# PCB-BI8-2x2.net
KiCad netlist of a schematic drawn in EAGLE
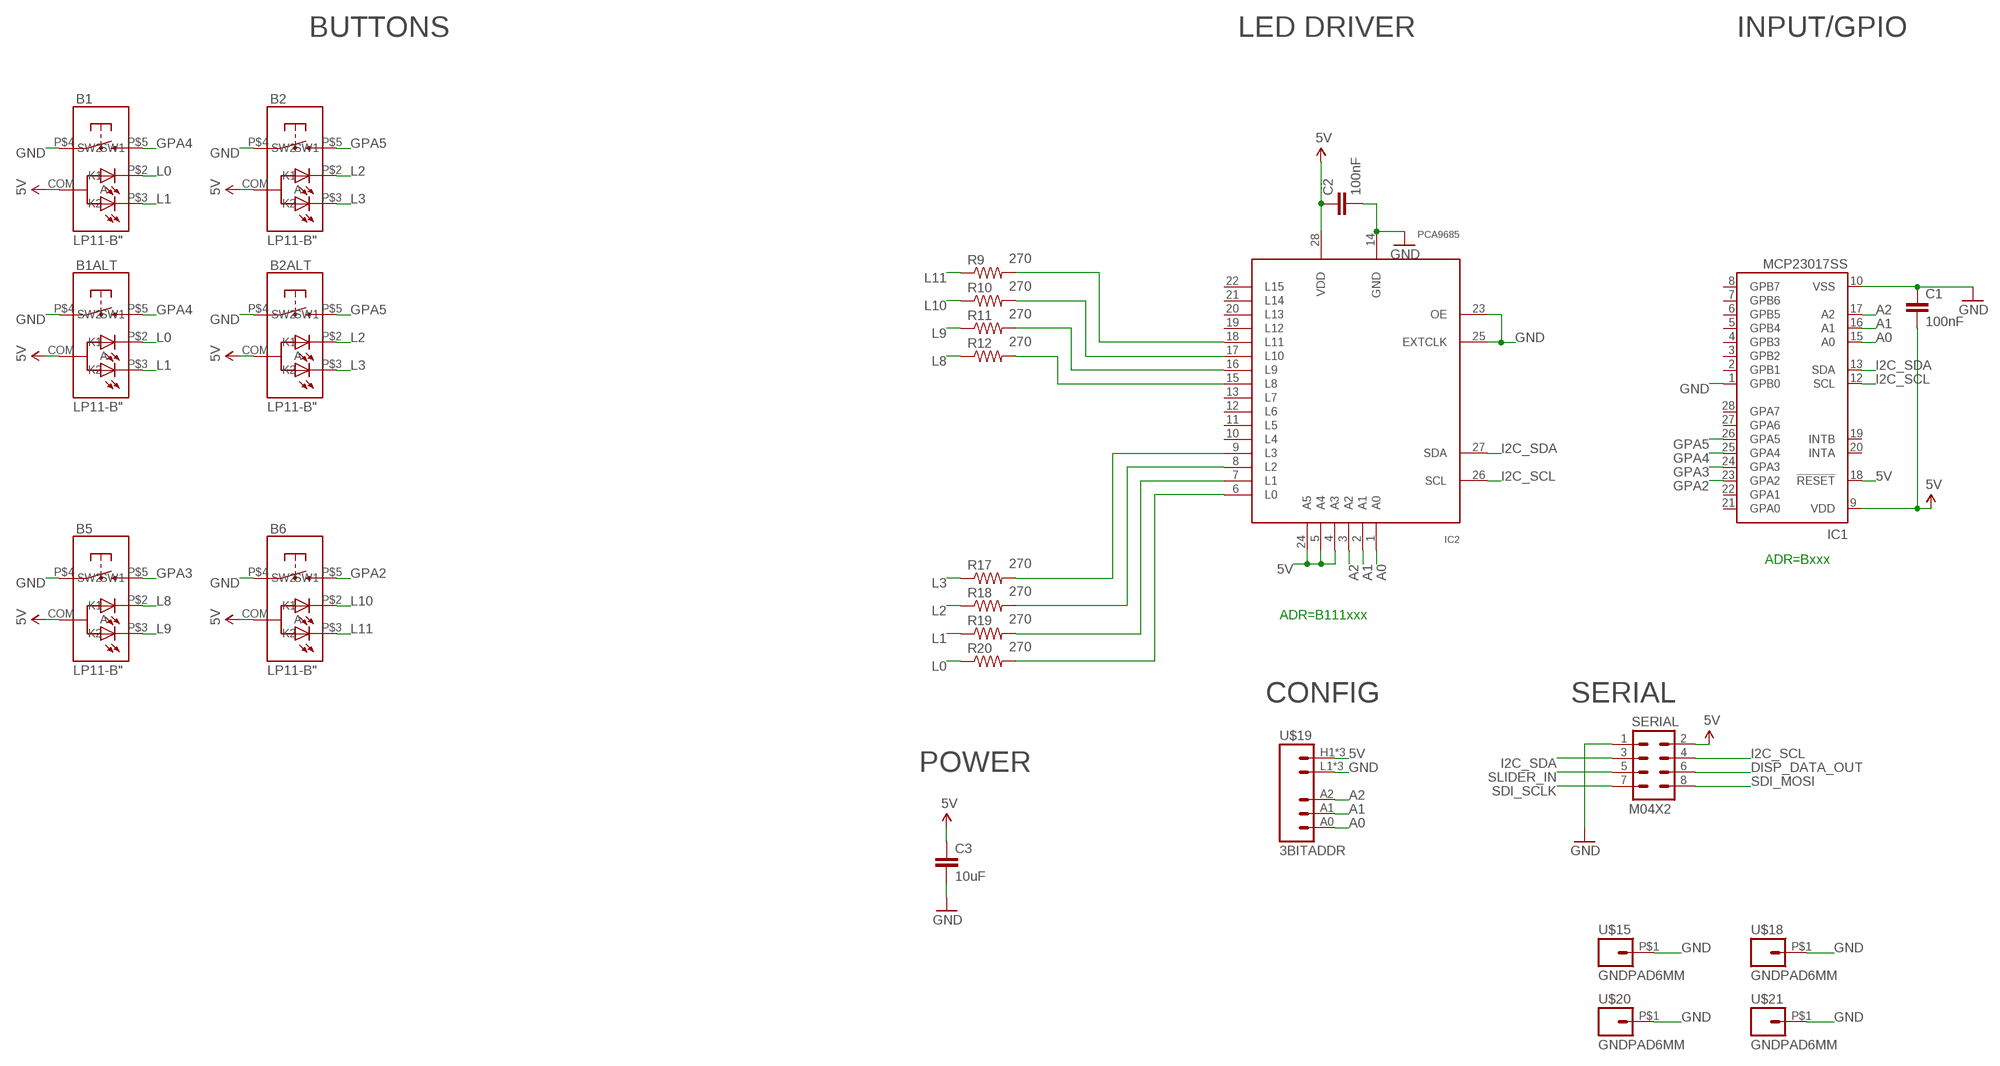
[diagram p0: schematic, sheet 1]

(export (version "E")
  (design (tool "Eeschema 10.0.6"))
  (components
    (comp (ref "B1")
      (value "LP11-B\"")
      (footprint "eagle-import:LP11")
      (libsource (lib "eagle-import") (part "LP11-B{dblquote}"))
    )
    (comp (ref "B1ALT")
      (value "LP11-B\"")
      (footprint "eagle-import:LP11")
      (libsource (lib "eagle-import") (part "LP11-B{dblquote}"))
    )
    (comp (ref "B2")
      (value "LP11-B\"")
      (footprint "eagle-import:LP11")
      (libsource (lib "eagle-import") (part "LP11-B{dblquote}"))
    )
    (comp (ref "B2ALT")
      (value "LP11-B\"")
      (footprint "eagle-import:LP11")
      (libsource (lib "eagle-import") (part "LP11-B{dblquote}"))
    )
    (comp (ref "B5")
      (value "LP11-B\"")
      (footprint "eagle-import:LP11")
      (libsource (lib "eagle-import") (part "LP11-B{dblquote}"))
    )
    (comp (ref "B6")
      (value "LP11-B\"")
      (footprint "eagle-import:LP11")
      (libsource (lib "eagle-import") (part "LP11-B{dblquote}"))
    )
    (comp (ref "C1")
      (value "100nF")
      (footprint "eagle-import:0603-CAP")
      (libsource (lib "eagle-import") (part "CAP0603-CAP"))
    )
    (comp (ref "C2")
      (value "100nF")
      (footprint "eagle-import:0603-CAP")
      (libsource (lib "eagle-import") (part "CAP0603-CAP"))
    )
    (comp (ref "C3")
      (value "10uF")
      (footprint "eagle-import:0805")
      (libsource (lib "eagle-import") (part "CAP0805"))
    )
    (comp (ref "IC1")
      (value "MCP23017SS")
      (footprint "eagle-import:SSOP28")
      (fields
        (field (name "MF") "MICROCHIP")
        (field (name "MPN") "MCP23017-E/SS")
        (field (name "MPN_1") "MCP23017-E/SS")
        (field (name "OC_FARNELL") "1467674")
        (field (name "OC_NEWARK") "31K2960")
      )
      (libsource (lib "eagle-import") (part "MCP23017SS"))
    )
    (comp (ref "IC2")
      (value "PCA9685")
      (footprint "eagle-import:TSSOP28")
      (libsource (lib "eagle-import") (part "PCA9685"))
    )
    (comp (ref "R9")
      (value "270")
      (footprint "eagle-import:0603-RES")
      (libsource (lib "eagle-import") (part "RESISTOR0603-RES"))
    )
    (comp (ref "R10")
      (value "270")
      (footprint "eagle-import:0603-RES")
      (libsource (lib "eagle-import") (part "RESISTOR0603-RES"))
    )
    (comp (ref "R11")
      (value "270")
      (footprint "eagle-import:0603-RES")
      (libsource (lib "eagle-import") (part "RESISTOR0603-RES"))
    )
    (comp (ref "R12")
      (value "270")
      (footprint "eagle-import:0603-RES")
      (libsource (lib "eagle-import") (part "RESISTOR0603-RES"))
    )
    (comp (ref "R17")
      (value "270")
      (footprint "eagle-import:0603-RES")
      (libsource (lib "eagle-import") (part "RESISTOR0603-RES"))
    )
    (comp (ref "R18")
      (value "270")
      (footprint "eagle-import:0603-RES")
      (libsource (lib "eagle-import") (part "RESISTOR0603-RES"))
    )
    (comp (ref "R19")
      (value "270")
      (footprint "eagle-import:0603-RES")
      (libsource (lib "eagle-import") (part "RESISTOR0603-RES"))
    )
    (comp (ref "R20")
      (value "270")
      (footprint "eagle-import:0603-RES")
      (libsource (lib "eagle-import") (part "RESISTOR0603-RES"))
    )
    (comp (ref "SERIAL")
      (value "M04X2")
      (footprint "eagle-import:2X4")
      (libsource (lib "eagle-import") (part "M04X2"))
    )
    (comp (ref "U$15")
      (value "GNDPAD6MM")
      (footprint "eagle-import:3.2MMPAD6MM")
      (libsource (lib "eagle-import") (part "GNDPAD6MM"))
    )
    (comp (ref "U$18")
      (value "GNDPAD6MM")
      (footprint "eagle-import:3.2MMPAD6MM")
      (libsource (lib "eagle-import") (part "GNDPAD6MM"))
    )
    (comp (ref "U$19")
      (value "3BITADDR")
      (footprint "eagle-import:3BITADDR")
      (libsource (lib "eagle-import") (part "3BITADDR"))
    )
    (comp (ref "U$20")
      (value "GNDPAD6MM")
      (footprint "eagle-import:3.2MMPAD6MM")
      (libsource (lib "eagle-import") (part "GNDPAD6MM"))
    )
    (comp (ref "U$21")
      (value "GNDPAD6MM")
      (footprint "eagle-import:3.2MMPAD6MM")
      (libsource (lib "eagle-import") (part "GNDPAD6MM"))
    )
  )
  (nets
    (net (code "1") (name "5V") (class "Default")
      (node (ref "B1") (pin "COM") (pinfunction "A_COM") (pintype "bidirectional"))
      (node (ref "B1ALT") (pin "COM") (pinfunction "A_COM") (pintype "bidirectional"))
      (node (ref "B2") (pin "COM") (pinfunction "A_COM") (pintype "bidirectional"))
      (node (ref "B2ALT") (pin "COM") (pinfunction "A_COM") (pintype "bidirectional"))
      (node (ref "B5") (pin "COM") (pinfunction "A_COM") (pintype "bidirectional"))
      (node (ref "B6") (pin "COM") (pinfunction "A_COM") (pintype "bidirectional"))
      (node (ref "C1") (pin "2") (pinfunction "2_2") (pintype "passive"))
      (node (ref "C2") (pin "1") (pinfunction "1_1") (pintype "passive"))
      (node (ref "C3") (pin "1") (pinfunction "1_1") (pintype "passive"))
      (node (ref "IC1") (pin "18") (pinfunction "~{RESET}_18") (pintype "input"))
      (node (ref "IC1") (pin "9") (pinfunction "VDD_9") (pintype "power_in"))
      (node (ref "IC2") (pin "24") (pinfunction "A5_24") (pintype "input"))
      (node (ref "IC2") (pin "28") (pinfunction "VDD_28") (pintype "power_in"))
      (node (ref "IC2") (pin "4") (pinfunction "A3_4") (pintype "input"))
      (node (ref "IC2") (pin "5") (pinfunction "A4_5") (pintype "input"))
      (node (ref "SERIAL") (pin "2") (pinfunction "2_2") (pintype "passive"))
      (node (ref "U$19") (pin "H1") (pinfunction "VCC_H1") (pintype "passive"))
      (node (ref "U$19") (pin "H2") (pinfunction "VCC_H2") (pintype "passive"))
      (node (ref "U$19") (pin "H3") (pinfunction "VCC_H3") (pintype "passive"))
    )
    (net (code "2") (name "A0") (class "Default")
      (node (ref "IC1") (pin "15") (pinfunction "A0_15") (pintype "input"))
      (node (ref "IC2") (pin "1") (pinfunction "A0_1") (pintype "input"))
      (node (ref "U$19") (pin "A0") (pinfunction "A0_A0") (pintype "passive"))
    )
    (net (code "3") (name "A1") (class "Default")
      (node (ref "IC1") (pin "16") (pinfunction "A1_16") (pintype "input"))
      (node (ref "IC2") (pin "2") (pinfunction "A1_2") (pintype "input"))
      (node (ref "U$19") (pin "A1") (pinfunction "A1_A1") (pintype "passive"))
    )
    (net (code "4") (name "A2") (class "Default")
      (node (ref "IC1") (pin "17") (pinfunction "A2_17") (pintype "input"))
      (node (ref "IC2") (pin "3") (pinfunction "A2_3") (pintype "input"))
      (node (ref "U$19") (pin "A2") (pinfunction "A2_A2") (pintype "passive"))
    )
    (net (code "5") (name "DISP_DATA_OUT") (class "Default")
      (node (ref "SERIAL") (pin "6") (pinfunction "6_6") (pintype "passive"))
    )
    (net (code "6") (name "GND") (class "Default")
      (node (ref "B1") (pin "P$4") (pinfunction "SW1_P$4") (pintype "bidirectional"))
      (node (ref "B1ALT") (pin "P$4") (pinfunction "SW1_P$4") (pintype "bidirectional"))
      (node (ref "B2") (pin "P$4") (pinfunction "SW1_P$4") (pintype "bidirectional"))
      (node (ref "B2ALT") (pin "P$4") (pinfunction "SW1_P$4") (pintype "bidirectional"))
      (node (ref "B5") (pin "P$4") (pinfunction "SW1_P$4") (pintype "bidirectional"))
      (node (ref "B6") (pin "P$4") (pinfunction "SW1_P$4") (pintype "bidirectional"))
      (node (ref "C1") (pin "1") (pinfunction "1_1") (pintype "passive"))
      (node (ref "C2") (pin "2") (pinfunction "2_2") (pintype "passive"))
      (node (ref "C3") (pin "2") (pinfunction "2_2") (pintype "passive"))
      (node (ref "IC1") (pin "1") (pinfunction "GPB0_1") (pintype "bidirectional"))
      (node (ref "IC1") (pin "10") (pinfunction "VSS_10") (pintype "power_in"))
      (node (ref "IC2") (pin "14") (pinfunction "GND_14") (pintype "power_in"))
      (node (ref "IC2") (pin "23") (pinfunction "OE_23") (pintype "input"))
      (node (ref "IC2") (pin "25") (pinfunction "EXTCLK_25") (pintype "input"))
      (node (ref "SERIAL") (pin "1") (pinfunction "1_1") (pintype "passive"))
      (node (ref "U$15") (pin "P$1") (pinfunction "1_P$1") (pintype "passive"))
      (node (ref "U$18") (pin "P$1") (pinfunction "1_P$1") (pintype "passive"))
      (node (ref "U$19") (pin "L1") (pinfunction "GND_L1") (pintype "passive"))
      (node (ref "U$19") (pin "L2") (pinfunction "GND_L2") (pintype "passive"))
      (node (ref "U$19") (pin "L3") (pinfunction "GND_L3") (pintype "passive"))
      (node (ref "U$20") (pin "P$1") (pinfunction "1_P$1") (pintype "passive"))
      (node (ref "U$21") (pin "P$1") (pinfunction "1_P$1") (pintype "passive"))
    )
    (net (code "7") (name "GPA2") (class "Default")
      (node (ref "B6") (pin "P$5") (pinfunction "SW2_P$5") (pintype "bidirectional"))
      (node (ref "IC1") (pin "23") (pinfunction "GPA2_23") (pintype "bidirectional"))
    )
    (net (code "8") (name "GPA3") (class "Default")
      (node (ref "B5") (pin "P$5") (pinfunction "SW2_P$5") (pintype "bidirectional"))
      (node (ref "IC1") (pin "24") (pinfunction "GPA3_24") (pintype "bidirectional"))
    )
    (net (code "9") (name "GPA4") (class "Default")
      (node (ref "B1") (pin "P$5") (pinfunction "SW2_P$5") (pintype "bidirectional"))
      (node (ref "B1ALT") (pin "P$5") (pinfunction "SW2_P$5") (pintype "bidirectional"))
      (node (ref "IC1") (pin "25") (pinfunction "GPA4_25") (pintype "bidirectional"))
    )
    (net (code "10") (name "GPA5") (class "Default")
      (node (ref "B2") (pin "P$5") (pinfunction "SW2_P$5") (pintype "bidirectional"))
      (node (ref "B2ALT") (pin "P$5") (pinfunction "SW2_P$5") (pintype "bidirectional"))
      (node (ref "IC1") (pin "26") (pinfunction "GPA5_26") (pintype "bidirectional"))
    )
    (net (code "11") (name "I2C_SCL") (class "Default")
      (node (ref "IC1") (pin "12") (pinfunction "SCL_12") (pintype "input"))
      (node (ref "IC2") (pin "26") (pinfunction "SCL_26") (pintype "input"))
      (node (ref "SERIAL") (pin "4") (pinfunction "4_4") (pintype "passive"))
    )
    (net (code "12") (name "I2C_SDA") (class "Default")
      (node (ref "IC1") (pin "13") (pinfunction "SDA_13") (pintype "bidirectional"))
      (node (ref "IC2") (pin "27") (pinfunction "SDA_27") (pintype "input"))
      (node (ref "SERIAL") (pin "3") (pinfunction "3_3") (pintype "passive"))
    )
    (net (code "13") (name "L0") (class "Default")
      (node (ref "B1") (pin "P$2") (pinfunction "K1_P$2") (pintype "bidirectional"))
      (node (ref "B1ALT") (pin "P$2") (pinfunction "K1_P$2") (pintype "bidirectional"))
      (node (ref "R20") (pin "1") (pinfunction "1_1") (pintype "passive"))
    )
    (net (code "14") (name "L1") (class "Default")
      (node (ref "B1") (pin "P$3") (pinfunction "K2_P$3") (pintype "bidirectional"))
      (node (ref "B1ALT") (pin "P$3") (pinfunction "K2_P$3") (pintype "bidirectional"))
      (node (ref "R19") (pin "1") (pinfunction "1_1") (pintype "passive"))
    )
    (net (code "15") (name "L2") (class "Default")
      (node (ref "B2") (pin "P$2") (pinfunction "K1_P$2") (pintype "bidirectional"))
      (node (ref "B2ALT") (pin "P$2") (pinfunction "K1_P$2") (pintype "bidirectional"))
      (node (ref "R18") (pin "1") (pinfunction "1_1") (pintype "passive"))
    )
    (net (code "16") (name "L3") (class "Default")
      (node (ref "B2") (pin "P$3") (pinfunction "K2_P$3") (pintype "bidirectional"))
      (node (ref "B2ALT") (pin "P$3") (pinfunction "K2_P$3") (pintype "bidirectional"))
      (node (ref "R17") (pin "1") (pinfunction "1_1") (pintype "passive"))
    )
    (net (code "17") (name "L8") (class "Default")
      (node (ref "B5") (pin "P$2") (pinfunction "K1_P$2") (pintype "bidirectional"))
      (node (ref "R12") (pin "1") (pinfunction "1_1") (pintype "passive"))
    )
    (net (code "18") (name "L9") (class "Default")
      (node (ref "B5") (pin "P$3") (pinfunction "K2_P$3") (pintype "bidirectional"))
      (node (ref "R11") (pin "1") (pinfunction "1_1") (pintype "passive"))
    )
    (net (code "19") (name "L10") (class "Default")
      (node (ref "B6") (pin "P$2") (pinfunction "K1_P$2") (pintype "bidirectional"))
      (node (ref "R10") (pin "1") (pinfunction "1_1") (pintype "passive"))
    )
    (net (code "20") (name "L11") (class "Default")
      (node (ref "B6") (pin "P$3") (pinfunction "K2_P$3") (pintype "bidirectional"))
      (node (ref "R9") (pin "1") (pinfunction "1_1") (pintype "passive"))
    )
    (net (code "21") (name "Net-(IC2-L0)") (class "Default")
      (node (ref "IC2") (pin "6") (pinfunction "L0_6") (pintype "output"))
      (node (ref "R20") (pin "2") (pinfunction "2_2") (pintype "passive"))
    )
    (net (code "22") (name "Net-(IC2-L1)") (class "Default")
      (node (ref "IC2") (pin "7") (pinfunction "L1_7") (pintype "output"))
      (node (ref "R19") (pin "2") (pinfunction "2_2") (pintype "passive"))
    )
    (net (code "23") (name "Net-(IC2-L2)") (class "Default")
      (node (ref "IC2") (pin "8") (pinfunction "L2_8") (pintype "output"))
      (node (ref "R18") (pin "2") (pinfunction "2_2") (pintype "passive"))
    )
    (net (code "24") (name "Net-(IC2-L3)") (class "Default")
      (node (ref "IC2") (pin "9") (pinfunction "L3_9") (pintype "output"))
      (node (ref "R17") (pin "2") (pinfunction "2_2") (pintype "passive"))
    )
    (net (code "25") (name "Net-(IC2-L8)") (class "Default")
      (node (ref "IC2") (pin "15") (pinfunction "L8_15") (pintype "output"))
      (node (ref "R12") (pin "2") (pinfunction "2_2") (pintype "passive"))
    )
    (net (code "26") (name "Net-(IC2-L9)") (class "Default")
      (node (ref "IC2") (pin "16") (pinfunction "L9_16") (pintype "output"))
      (node (ref "R11") (pin "2") (pinfunction "2_2") (pintype "passive"))
    )
    (net (code "27") (name "Net-(IC2-L10)") (class "Default")
      (node (ref "IC2") (pin "17") (pinfunction "L10_17") (pintype "output"))
      (node (ref "R10") (pin "2") (pinfunction "2_2") (pintype "passive"))
    )
    (net (code "28") (name "Net-(IC2-L11)") (class "Default")
      (node (ref "IC2") (pin "18") (pinfunction "L11_18") (pintype "output"))
      (node (ref "R9") (pin "2") (pinfunction "2_2") (pintype "passive"))
    )
    (net (code "29") (name "SDI_MOSI") (class "Default")
      (node (ref "SERIAL") (pin "8") (pinfunction "8_8") (pintype "passive"))
    )
    (net (code "30") (name "SDI_SCLK") (class "Default")
      (node (ref "SERIAL") (pin "7") (pinfunction "7_7") (pintype "passive"))
    )
    (net (code "31") (name "SLIDER_IN") (class "Default")
      (node (ref "SERIAL") (pin "5") (pinfunction "5_5") (pintype "passive"))
    )
    (net (code "32") (name "unconnected-(IC1-GPA0-Pad21)") (class "Default")
      (node (ref "IC1") (pin "21") (pinfunction "GPA0_21") (pintype "bidirectional"))
    )
    (net (code "33") (name "unconnected-(IC1-GPA1-Pad22)") (class "Default")
      (node (ref "IC1") (pin "22") (pinfunction "GPA1_22") (pintype "bidirectional"))
    )
    (net (code "34") (name "unconnected-(IC1-GPA6-Pad27)") (class "Default")
      (node (ref "IC1") (pin "27") (pinfunction "GPA6_27") (pintype "bidirectional"))
    )
    (net (code "35") (name "unconnected-(IC1-GPA7-Pad28)") (class "Default")
      (node (ref "IC1") (pin "28") (pinfunction "GPA7_28") (pintype "bidirectional"))
    )
    (net (code "36") (name "unconnected-(IC1-GPB1-Pad2)") (class "Default")
      (node (ref "IC1") (pin "2") (pinfunction "GPB1_2") (pintype "bidirectional"))
    )
    (net (code "37") (name "unconnected-(IC1-GPB2-Pad3)") (class "Default")
      (node (ref "IC1") (pin "3") (pinfunction "GPB2_3") (pintype "bidirectional"))
    )
    (net (code "38") (name "unconnected-(IC1-GPB3-Pad4)") (class "Default")
      (node (ref "IC1") (pin "4") (pinfunction "GPB3_4") (pintype "bidirectional"))
    )
    (net (code "39") (name "unconnected-(IC1-GPB4-Pad5)") (class "Default")
      (node (ref "IC1") (pin "5") (pinfunction "GPB4_5") (pintype "bidirectional"))
    )
    (net (code "40") (name "unconnected-(IC1-GPB5-Pad6)") (class "Default")
      (node (ref "IC1") (pin "6") (pinfunction "GPB5_6") (pintype "bidirectional"))
    )
    (net (code "41") (name "unconnected-(IC1-GPB6-Pad7)") (class "Default")
      (node (ref "IC1") (pin "7") (pinfunction "GPB6_7") (pintype "bidirectional"))
    )
    (net (code "42") (name "unconnected-(IC1-GPB7-Pad8)") (class "Default")
      (node (ref "IC1") (pin "8") (pinfunction "GPB7_8") (pintype "bidirectional"))
    )
    (net (code "43") (name "unconnected-(IC1-INTA-Pad20)") (class "Default")
      (node (ref "IC1") (pin "20") (pinfunction "INTA_20") (pintype "output"))
    )
    (net (code "44") (name "unconnected-(IC1-INTB-Pad19)") (class "Default")
      (node (ref "IC1") (pin "19") (pinfunction "INTB_19") (pintype "output"))
    )
    (net (code "45") (name "unconnected-(IC2-L4-Pad10)") (class "Default")
      (node (ref "IC2") (pin "10") (pinfunction "L4_10") (pintype "output"))
    )
    (net (code "46") (name "unconnected-(IC2-L5-Pad11)") (class "Default")
      (node (ref "IC2") (pin "11") (pinfunction "L5_11") (pintype "output"))
    )
    (net (code "47") (name "unconnected-(IC2-L6-Pad12)") (class "Default")
      (node (ref "IC2") (pin "12") (pinfunction "L6_12") (pintype "output"))
    )
    (net (code "48") (name "unconnected-(IC2-L7-Pad13)") (class "Default")
      (node (ref "IC2") (pin "13") (pinfunction "L7_13") (pintype "output"))
    )
    (net (code "49") (name "unconnected-(IC2-L12-Pad19)") (class "Default")
      (node (ref "IC2") (pin "19") (pinfunction "L12_19") (pintype "output"))
    )
    (net (code "50") (name "unconnected-(IC2-L13-Pad20)") (class "Default")
      (node (ref "IC2") (pin "20") (pinfunction "L13_20") (pintype "output"))
    )
    (net (code "51") (name "unconnected-(IC2-L14-Pad21)") (class "Default")
      (node (ref "IC2") (pin "21") (pinfunction "L14_21") (pintype "output"))
    )
    (net (code "52") (name "unconnected-(IC2-L15-Pad22)") (class "Default")
      (node (ref "IC2") (pin "22") (pinfunction "L15_22") (pintype "output"))
    )
  )
)
